# PSRAM.net
KiCad netlist of a schematic drawn in Altium Designer
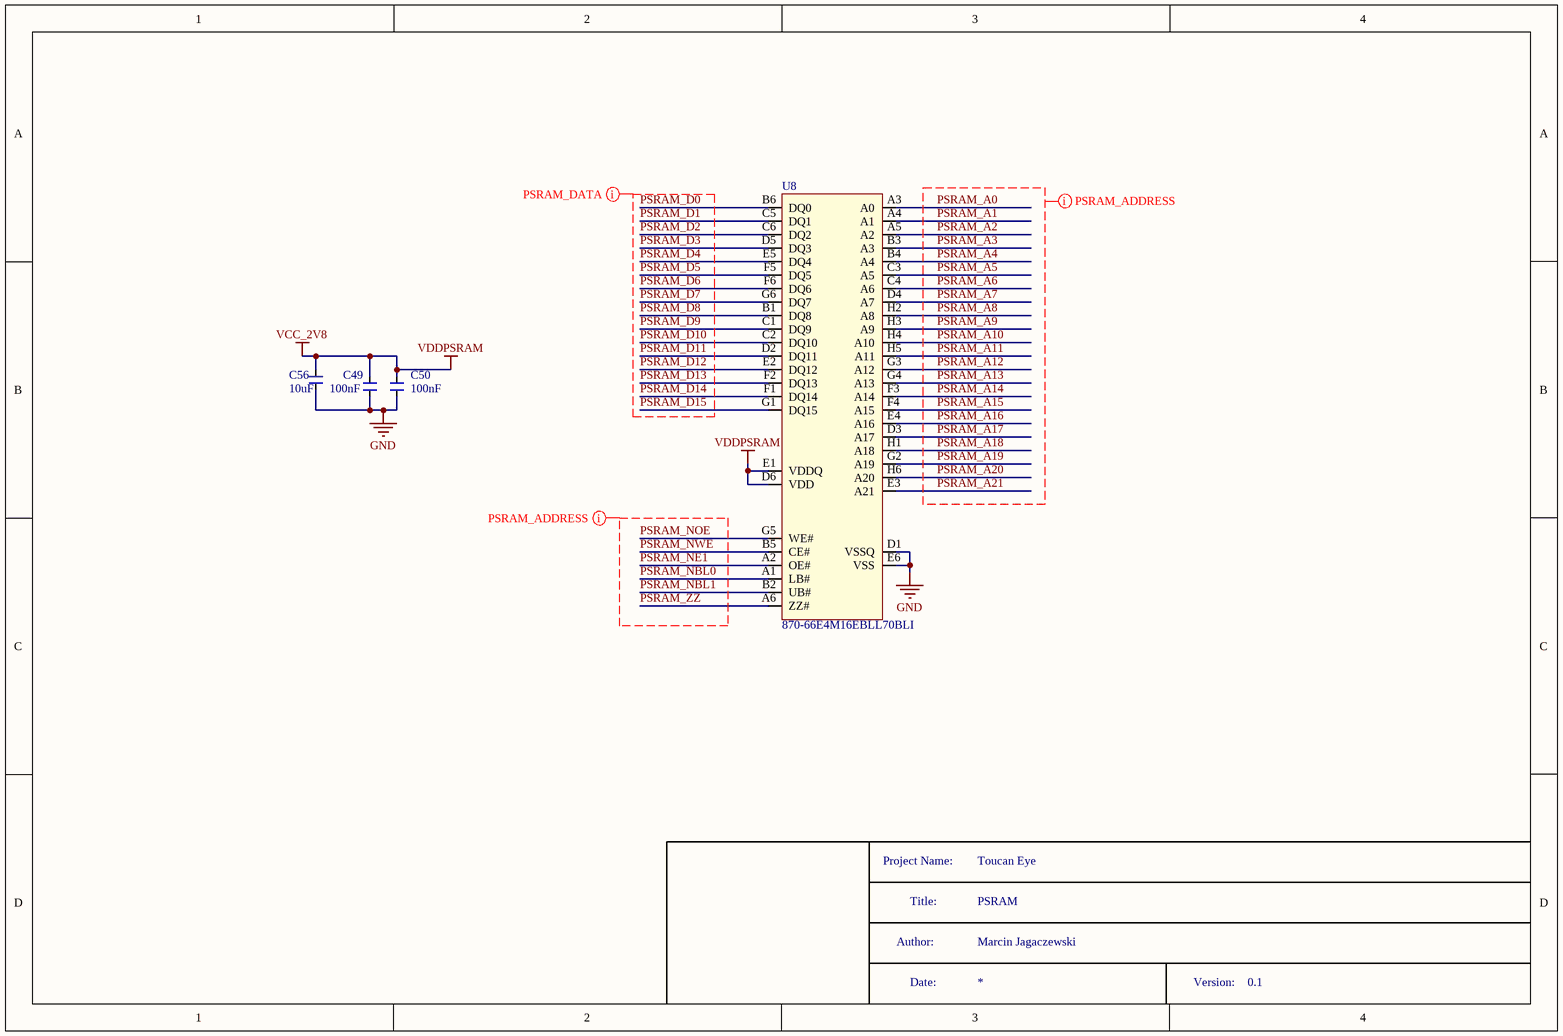
[diagram p0: PSRAM.SchDoc]

(export (version "E")
  (design (tool "Eeschema 10.0.6"))
  (components
    (comp (ref "C49")
      (value "C0201_100n_GRM033R6YA104KE14D")
      (footprint "C_0201")
      (description "Multilayer Ceramic Capacitors MLCC - SMD/SMT 0201 0.10uF 35volts *Derate Voltage/Temp")
      (fields
        (field (name "MANUFACTURER") "Murata")
        (field (name "MANUFACTURER PART NUMBER") "GRM033R6YA104KE14D")
        (field (name "CAPACITANCE") "100nF")
      )
      (libsource (lib "CAP") (part "C0201_100n_GRM033R6YA104KE14D"))
    )
    (comp (ref "C50")
      (value "C0201_100n_GRM033R6YA104KE14D")
      (footprint "C_0201")
      (description "Multilayer Ceramic Capacitors MLCC - SMD/SMT 0201 0.10uF 35volts *Derate Voltage/Temp")
      (fields
        (field (name "MANUFACTURER") "Murata")
        (field (name "MANUFACTURER PART NUMBER") "GRM033R6YA104KE14D")
        (field (name "CAPACITANCE") "100nF")
      )
      (libsource (lib "CAP") (part "C0201_100n_GRM033R6YA104KE14D"))
    )
    (comp (ref "C56")
      (value "C0402_10u_GRM155C80J106ME11D")
      (footprint "C_0402")
      (description "10µF 6.3V Ceramic Capacitor X6S 0402 (1005 Metric) 0.039\" L x 0.020\" W (1.00mm x 0.50mm)")
      (fields
        (field (name "MANUFACTURER") "Murata")
        (field (name "MANUFACTURER PART NUMBER") "GRM155C80J106ME11D")
        (field (name "CAPACITANCE") "10uF")
      )
      (libsource (lib "CAP") (part "C0402_10u_GRM155C80J106ME11D"))
    )
    (comp (ref "U8")
      (value "IS66WVE4M16EBLL-70BLI")
      (footprint "BGA48C75P6X8_600X800X120")
      (description "PSRAM Async 64M-Bit 4M x 16 70ns 48-Pin TFBGA")
      (fields
        (field (name "MANUFACTURER") "ISSI")
        (field (name "SUPPLIER PART NUMBER 1") "870-66E4M16EBLL70BLI")
      )
      (libsource (lib "CHIP") (part "IS66WVE4M16EBLL-70BLI"))
    )
  )
  (nets
    (net (code "1") (name "/PSRAM_A0") (class "Default")
      (node (ref "U8") (pin "A3") (pinfunction "A0_A3") (pintype "passive"))
    )
    (net (code "2") (name "/PSRAM_A1") (class "Default")
      (node (ref "U8") (pin "A4") (pinfunction "A1_A4") (pintype "passive"))
    )
    (net (code "3") (name "/PSRAM_A2") (class "Default")
      (node (ref "U8") (pin "A5") (pinfunction "A2_A5") (pintype "passive"))
    )
    (net (code "4") (name "/PSRAM_A3") (class "Default")
      (node (ref "U8") (pin "B3") (pinfunction "A3_B3") (pintype "passive"))
    )
    (net (code "5") (name "/PSRAM_A4") (class "Default")
      (node (ref "U8") (pin "B4") (pinfunction "A4_B4") (pintype "passive"))
    )
    (net (code "6") (name "/PSRAM_A5") (class "Default")
      (node (ref "U8") (pin "C3") (pinfunction "A5_C3") (pintype "passive"))
    )
    (net (code "7") (name "/PSRAM_A6") (class "Default")
      (node (ref "U8") (pin "C4") (pinfunction "A6_C4") (pintype "passive"))
    )
    (net (code "8") (name "/PSRAM_A7") (class "Default")
      (node (ref "U8") (pin "D4") (pinfunction "A7_D4") (pintype "passive"))
    )
    (net (code "9") (name "/PSRAM_A8") (class "Default")
      (node (ref "U8") (pin "H2") (pinfunction "A8_H2") (pintype "passive"))
    )
    (net (code "10") (name "/PSRAM_A9") (class "Default")
      (node (ref "U8") (pin "H3") (pinfunction "A9_H3") (pintype "passive"))
    )
    (net (code "11") (name "/PSRAM_A10") (class "Default")
      (node (ref "U8") (pin "H4") (pinfunction "A10_H4") (pintype "passive"))
    )
    (net (code "12") (name "/PSRAM_A11") (class "Default")
      (node (ref "U8") (pin "H5") (pinfunction "A11_H5") (pintype "passive"))
    )
    (net (code "13") (name "/PSRAM_A12") (class "Default")
      (node (ref "U8") (pin "G3") (pinfunction "A12_G3") (pintype "passive"))
    )
    (net (code "14") (name "/PSRAM_A13") (class "Default")
      (node (ref "U8") (pin "G4") (pinfunction "A13_G4") (pintype "passive"))
    )
    (net (code "15") (name "/PSRAM_A14") (class "Default")
      (node (ref "U8") (pin "F3") (pinfunction "A14_F3") (pintype "passive"))
    )
    (net (code "16") (name "/PSRAM_A15") (class "Default")
      (node (ref "U8") (pin "F4") (pinfunction "A15_F4") (pintype "passive"))
    )
    (net (code "17") (name "/PSRAM_A16") (class "Default")
      (node (ref "U8") (pin "E4") (pinfunction "A16_E4") (pintype "passive"))
    )
    (net (code "18") (name "/PSRAM_A17") (class "Default")
      (node (ref "U8") (pin "D3") (pinfunction "A17_D3") (pintype "passive"))
    )
    (net (code "19") (name "/PSRAM_A18") (class "Default")
      (node (ref "U8") (pin "H1") (pinfunction "A18_H1") (pintype "passive"))
    )
    (net (code "20") (name "/PSRAM_A19") (class "Default")
      (node (ref "U8") (pin "G2") (pinfunction "A19_G2") (pintype "passive"))
    )
    (net (code "21") (name "/PSRAM_A20") (class "Default")
      (node (ref "U8") (pin "H6") (pinfunction "A20_H6") (pintype "passive"))
    )
    (net (code "22") (name "/PSRAM_A21") (class "Default")
      (node (ref "U8") (pin "E3") (pinfunction "A21_E3") (pintype "passive"))
    )
    (net (code "23") (name "/PSRAM_D0") (class "Default")
      (node (ref "U8") (pin "B6") (pinfunction "DQ0_B6") (pintype "passive"))
    )
    (net (code "24") (name "/PSRAM_D1") (class "Default")
      (node (ref "U8") (pin "C5") (pinfunction "DQ1_C5") (pintype "passive"))
    )
    (net (code "25") (name "/PSRAM_D2") (class "Default")
      (node (ref "U8") (pin "C6") (pinfunction "DQ2_C6") (pintype "passive"))
    )
    (net (code "26") (name "/PSRAM_D3") (class "Default")
      (node (ref "U8") (pin "D5") (pinfunction "DQ3_D5") (pintype "passive"))
    )
    (net (code "27") (name "/PSRAM_D4") (class "Default")
      (node (ref "U8") (pin "E5") (pinfunction "DQ4_E5") (pintype "passive"))
    )
    (net (code "28") (name "/PSRAM_D5") (class "Default")
      (node (ref "U8") (pin "F5") (pinfunction "DQ5_F5") (pintype "passive"))
    )
    (net (code "29") (name "/PSRAM_D6") (class "Default")
      (node (ref "U8") (pin "F6") (pinfunction "DQ6_F6") (pintype "passive"))
    )
    (net (code "30") (name "/PSRAM_D7") (class "Default")
      (node (ref "U8") (pin "G6") (pinfunction "DQ7_G6") (pintype "passive"))
    )
    (net (code "31") (name "/PSRAM_D8") (class "Default")
      (node (ref "U8") (pin "B1") (pinfunction "DQ8_B1") (pintype "passive"))
    )
    (net (code "32") (name "/PSRAM_D9") (class "Default")
      (node (ref "U8") (pin "C1") (pinfunction "DQ9_C1") (pintype "passive"))
    )
    (net (code "33") (name "/PSRAM_D10") (class "Default")
      (node (ref "U8") (pin "C2") (pinfunction "DQ10_C2") (pintype "passive"))
    )
    (net (code "34") (name "/PSRAM_D11") (class "Default")
      (node (ref "U8") (pin "D2") (pinfunction "DQ11_D2") (pintype "passive"))
    )
    (net (code "35") (name "/PSRAM_D12") (class "Default")
      (node (ref "U8") (pin "E2") (pinfunction "DQ12_E2") (pintype "passive"))
    )
    (net (code "36") (name "/PSRAM_D13") (class "Default")
      (node (ref "U8") (pin "F2") (pinfunction "DQ13_F2") (pintype "passive"))
    )
    (net (code "37") (name "/PSRAM_D14") (class "Default")
      (node (ref "U8") (pin "F1") (pinfunction "DQ14_F1") (pintype "passive"))
    )
    (net (code "38") (name "/PSRAM_D15") (class "Default")
      (node (ref "U8") (pin "G1") (pinfunction "DQ15_G1") (pintype "passive"))
    )
    (net (code "39") (name "/PSRAM_NBL0") (class "Default")
      (node (ref "U8") (pin "A1") (pinfunction "LB#_A1") (pintype "passive"))
    )
    (net (code "40") (name "/PSRAM_NBL1") (class "Default")
      (node (ref "U8") (pin "B2") (pinfunction "UB#_B2") (pintype "passive"))
    )
    (net (code "41") (name "/PSRAM_NE1") (class "Default")
      (node (ref "U8") (pin "A2") (pinfunction "OE#_A2") (pintype "passive"))
    )
    (net (code "42") (name "/PSRAM_NOE") (class "Default")
      (node (ref "U8") (pin "G5") (pinfunction "WE#_G5") (pintype "passive"))
    )
    (net (code "43") (name "/PSRAM_NWE") (class "Default")
      (node (ref "U8") (pin "B5") (pinfunction "CE#_B5") (pintype "passive"))
    )
    (net (code "44") (name "/PSRAM_ZZ") (class "Default")
      (node (ref "U8") (pin "A6") (pinfunction "ZZ#_A6") (pintype "passive"))
    )
    (net (code "45") (name "GND") (class "Default")
      (node (ref "C49") (pin "1") (pinfunction "1_1") (pintype "passive"))
      (node (ref "C50") (pin "1") (pinfunction "1_1") (pintype "passive"))
      (node (ref "C56") (pin "1") (pinfunction "1_1") (pintype "passive"))
      (node (ref "U8") (pin "D1") (pinfunction "VSSQ_D1") (pintype "passive"))
      (node (ref "U8") (pin "E6") (pinfunction "VSS_E6") (pintype "passive"))
    )
    (net (code "46") (name "VCC_2V8") (class "Default")
      (node (ref "C49") (pin "2") (pinfunction "2_2") (pintype "passive"))
      (node (ref "C50") (pin "2") (pinfunction "2_2") (pintype "passive"))
      (node (ref "C56") (pin "2") (pinfunction "2_2") (pintype "passive"))
      (node (ref "U8") (pin "D6") (pinfunction "VDD_D6") (pintype "passive"))
      (node (ref "U8") (pin "E1") (pinfunction "VDDQ_E1") (pintype "passive"))
    )
  )
)
